# SH2_-_CONNECTORS.net
KiCad netlist of a schematic drawn in Altium Designer
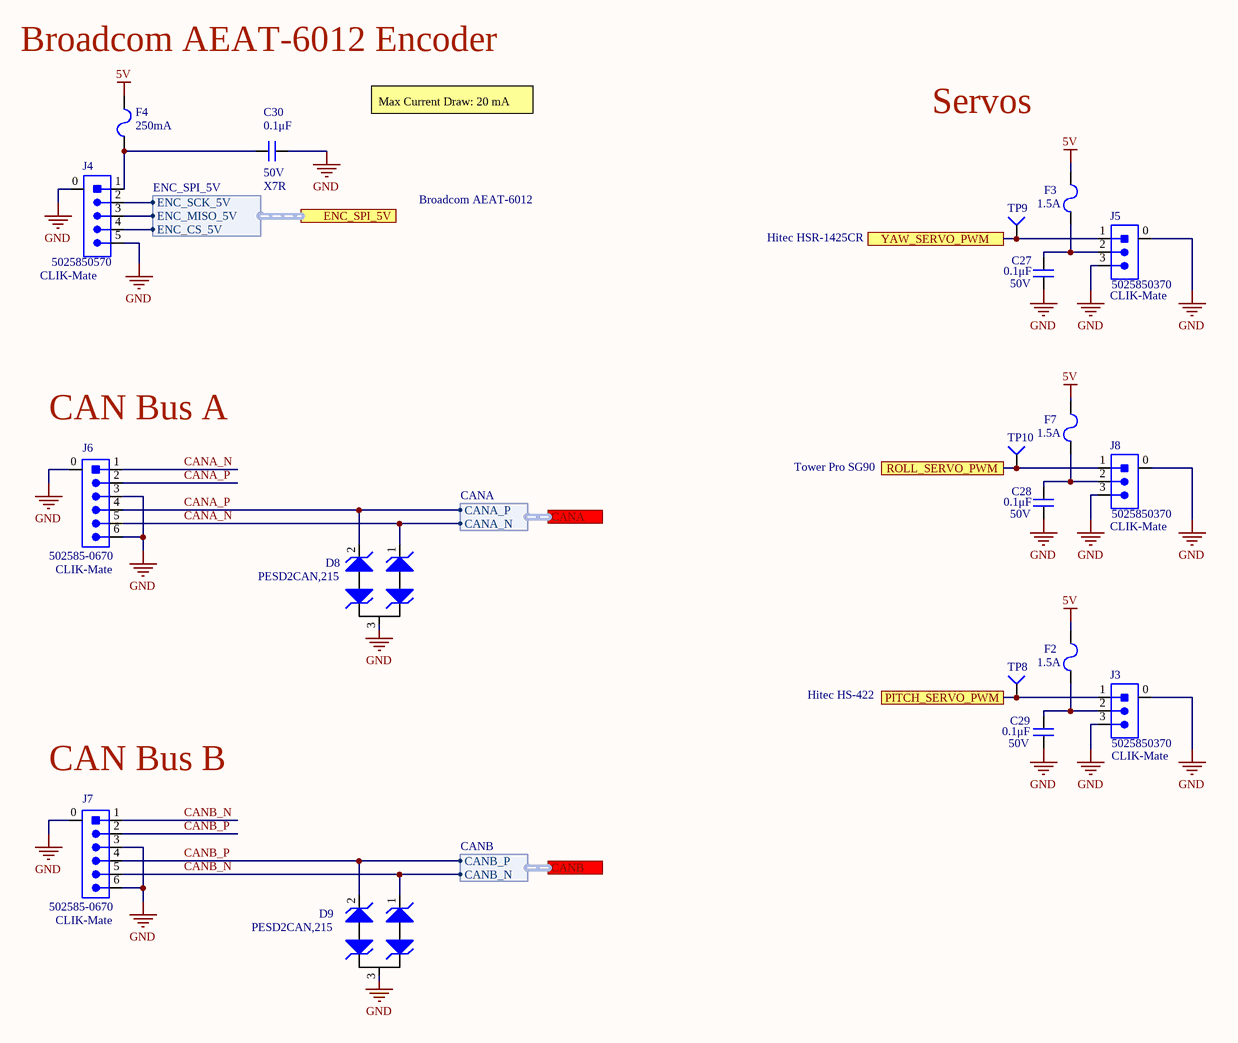
[diagram p0: SH2 - CONNECTORS.SchDoc]

(export (version "E")
  (design (tool "Eeschema 10.0.6"))
  (components
    (comp (ref "C27")
      (value "0.1μF")
      (footprint "CAP0603")
      (description "CAP CER 0.1UF 50V X7R 0603")
      (fields (field (name "VOLTAGE RATING") "50V") (field (name "Comment") "CAP_0.1uF_50V_0603"))
      (libsource (lib "UWRT_Schematic_Library_2020") (part "CAP_0.1uF_50V_0603"))
    )
    (comp (ref "C28")
      (value "0.1μF")
      (footprint "CAP0603")
      (description "CAP CER 0.1UF 50V X7R 0603")
      (fields (field (name "VOLTAGE RATING") "50V") (field (name "Comment") "CAP_0.1uF_50V_0603"))
      (libsource (lib "UWRT_Schematic_Library_2020") (part "CAP_0.1uF_50V_0603"))
    )
    (comp (ref "C29")
      (value "0.1μF")
      (footprint "CAP0603")
      (description "CAP CER 0.1UF 50V X7R 0603")
      (fields (field (name "VOLTAGE RATING") "50V") (field (name "Comment") "CAP_0.1uF_50V_0603"))
      (libsource (lib "UWRT_Schematic_Library_2020") (part "CAP_0.1uF_50V_0603"))
    )
    (comp (ref "C30")
      (value "0.1μF")
      (footprint "CAP0603")
      (description "CAP CER 0.1UF 50V X7R 0603")
      (fields
        (field (name "DIELECTRIC") "X7R")
        (field (name "VOLTAGE RATING") "50V")
        (field (name "Comment") "CAP_0.1uF_50V_0603")
      )
      (libsource (lib "UWRT_Schematic_Library_2020") (part "CAP_0.1uF_50V_0603"))
    )
    (comp (ref "D8")
      (value "TVS_DIODE_CAN")
      (footprint "TVS_DIODE_CAN")
      (description "TVS DIODE 24V 41V SOT323-3")
      (fields (field (name "MANUFACTURER PART NUMBER 1") "PESD2CAN,215"))
      (libsource (lib "UWRT_Schematic_Library_2020") (part "TVS_DIODE_CAN"))
    )
    (comp (ref "D9")
      (value "TVS_DIODE_CAN")
      (footprint "TVS_DIODE_CAN")
      (description "TVS DIODE 24V 41V SOT323-3")
      (fields (field (name "MANUFACTURER PART NUMBER 1") "PESD2CAN,215"))
      (libsource (lib "UWRT_Schematic_Library_2020") (part "TVS_DIODE_CAN"))
    )
    (comp (ref "F2")
      (value "FUSE_1.5A_1206")
      (footprint "FUSE_1206")
      (description "FUSE SMD 1.5A 63V")
      (fields (field (name "CURRENT RATING") "1.5A"))
      (libsource (lib "UWRT_Schematic_Library_2020") (part "FUSE_1.5A_1206"))
    )
    (comp (ref "F3")
      (value "FUSE_1.5A_1206")
      (footprint "FUSE_1206")
      (description "FUSE SMD 1.5A 63V")
      (fields (field (name "CURRENT RATING") "1.5A"))
      (libsource (lib "UWRT_Schematic_Library_2020") (part "FUSE_1.5A_1206"))
    )
    (comp (ref "F4")
      (value "FUSE_250mA_0603")
      (footprint "FUSE_0603")
      (description "FUSE SMD 250mA 32V")
      (fields (field (name "CURRENT RATING") "250mA"))
      (libsource (lib "UWRT_Schematic_Library_2020") (part "FUSE_250mA_0603"))
    )
    (comp (ref "F7")
      (value "FUSE_1.5A_1206")
      (footprint "FUSE_1206")
      (description "FUSE SMD 1.5A 63V")
      (fields (field (name "CURRENT RATING") "1.5A"))
      (libsource (lib "UWRT_Schematic_Library_2020") (part "FUSE_1.5A_1206"))
    )
    (comp (ref "J3")
      (value "CON_3M_SM_RA")
      (footprint "MOLEX-5025850370")
      (description "CONN RCPT 3POS 0.059 TIN SMD R/A")
      (fields (field (name "MANUFACTURER PART NUMBER 1") "5025850370") (field (name "FAMILY") "CLIK-Mate"))
      (libsource (lib "UWRT_Schematic_Library_2020") (part "CON_3M_SM_RA"))
    )
    (comp (ref "J4")
      (value "CON_5M_SM_RA")
      (footprint "MOLEX-5025850570")
      (description "CONN HEADER SMD RIGHT ANGLE 1.5MM PITCH")
      (fields (field (name "MANUFACTURER PART NUMBER 1") "5025850570") (field (name "FAMILY") "CLIK-Mate"))
      (libsource (lib "UWRT_Schematic_Library_2020") (part "CON_5M_SM_RA"))
    )
    (comp (ref "J5")
      (value "CON_3M_SM_RA")
      (footprint "MOLEX-5025850370")
      (description "CONN RCPT 3POS 0.059 TIN SMD R/A")
      (fields (field (name "MANUFACTURER PART NUMBER 1") "5025850370") (field (name "FAMILY") "CLIK-Mate"))
      (libsource (lib "UWRT_Schematic_Library_2020") (part "CON_3M_SM_RA"))
    )
    (comp (ref "J6")
      (value "CON_6M_SM_RA_1.5mm")
      (footprint "MOLEX-5025850670")
      (description "CONN HEADER SMD RIGHT ANGLE 1.5 MM PITCH")
      (fields
        (field (name "MANUFACTURER") "Molex")
        (field (name "FAMILY") "CLIK-Mate")
        (field (name "MANUFACTOR NUMBER") "502585-0670")
      )
      (libsource (lib "UWRT_Schematic_Library_2020") (part "CON_6M_SM_RA_1.5mm"))
    )
    (comp (ref "J7")
      (value "CON_6M_SM_RA_1.5mm")
      (footprint "MOLEX-5025850670")
      (description "CONN HEADER SMD RIGHT ANGLE 1.5 MM PITCH")
      (fields
        (field (name "MANUFACTURER") "Molex")
        (field (name "FAMILY") "CLIK-Mate")
        (field (name "MANUFACTOR NUMBER") "502585-0670")
      )
      (libsource (lib "UWRT_Schematic_Library_2020") (part "CON_6M_SM_RA_1.5mm"))
    )
    (comp (ref "J8")
      (value "CON_3M_SM_RA")
      (footprint "MOLEX-5025850370")
      (description "CONN RCPT 3POS 0.059 TIN SMD R/A")
      (fields (field (name "MANUFACTURER PART NUMBER 1") "5025850370") (field (name "FAMILY") "CLIK-Mate"))
      (libsource (lib "UWRT_Schematic_Library_2020") (part "CON_3M_SM_RA"))
    )
    (comp (ref "TP8")
      (value "TESTPOINT_1MM_CIRCLE")
      (footprint "TESTPOINT_CIRCLE_1MM")
      (description "TESTPOINT 1MM CIRCLE")
      (libsource (lib "UWRT_Schematic_Library_2020") (part "TESTPOINT_1MM_CIRCLE"))
    )
    (comp (ref "TP9")
      (value "TESTPOINT_1MM_CIRCLE")
      (footprint "TESTPOINT_CIRCLE_1MM")
      (description "TESTPOINT 1MM CIRCLE")
      (libsource (lib "UWRT_Schematic_Library_2020") (part "TESTPOINT_1MM_CIRCLE"))
    )
    (comp (ref "TP10")
      (value "TESTPOINT_1MM_CIRCLE")
      (footprint "TESTPOINT_CIRCLE_1MM")
      (description "TESTPOINT 1MM CIRCLE")
      (libsource (lib "UWRT_Schematic_Library_2020") (part "TESTPOINT_1MM_CIRCLE"))
    )
  )
  (nets
    (net (code "4") (name "/CANA_N") (class "Default")
      (node (ref "D8") (pin "1") (pinfunction "1_1") (pintype "passive"))
      (node (ref "J6") (pin "1") (pinfunction "1_1") (pintype "passive"))
      (node (ref "J6") (pin "5") (pinfunction "5_5") (pintype "passive"))
    )
    (net (code "5") (name "/CANA_P") (class "Default")
      (node (ref "D8") (pin "2") (pinfunction "2_2") (pintype "passive"))
      (node (ref "J6") (pin "2") (pinfunction "2_2") (pintype "passive"))
      (node (ref "J6") (pin "4") (pinfunction "4_4") (pintype "passive"))
    )
    (net (code "6") (name "/CANB_N") (class "Default")
      (node (ref "D9") (pin "1") (pinfunction "1_1") (pintype "passive"))
      (node (ref "J7") (pin "1") (pinfunction "1_1") (pintype "passive"))
      (node (ref "J7") (pin "5") (pinfunction "5_5") (pintype "passive"))
    )
    (net (code "7") (name "/CANB_P") (class "Default")
      (node (ref "D9") (pin "2") (pinfunction "2_2") (pintype "passive"))
      (node (ref "J7") (pin "2") (pinfunction "2_2") (pintype "passive"))
      (node (ref "J7") (pin "4") (pinfunction "4_4") (pintype "passive"))
    )
    (net (code "8") (name "/ENC_CS_5V") (class "Default")
      (node (ref "J4") (pin "4") (pinfunction "4_4") (pintype "passive"))
    )
    (net (code "9") (name "/ENC_MISO_5V") (class "Default")
      (node (ref "J4") (pin "3") (pinfunction "3_3") (pintype "passive"))
    )
    (net (code "10") (name "/ENC_SCK_5V") (class "Default")
      (node (ref "J4") (pin "2") (pinfunction "2_2") (pintype "passive"))
    )
    (net (code "11") (name "/PITCH_SERVO_PWM") (class "Default")
      (node (ref "J3") (pin "1") (pinfunction "1_1") (pintype "passive"))
      (node (ref "TP8") (pin "1") (pinfunction "=value_1") (pintype "passive"))
    )
    (net (code "12") (name "/ROLL_SERVO_PWM") (class "Default")
      (node (ref "J8") (pin "1") (pinfunction "1_1") (pintype "passive"))
      (node (ref "TP10") (pin "1") (pinfunction "=value_1") (pintype "passive"))
    )
    (net (code "13") (name "/YAW_SERVO_PWM") (class "Default")
      (node (ref "J5") (pin "1") (pinfunction "1_1") (pintype "passive"))
      (node (ref "TP9") (pin "1") (pinfunction "=value_1") (pintype "passive"))
    )
    (net (code "17") (name "5V") (class "Default")
      (node (ref "F2") (pin "2") (pinfunction "2_2") (pintype "passive"))
      (node (ref "F3") (pin "2") (pinfunction "2_2") (pintype "passive"))
      (node (ref "F4") (pin "2") (pinfunction "2_2") (pintype "passive"))
      (node (ref "F7") (pin "2") (pinfunction "2_2") (pintype "passive"))
    )
    (net (code "18") (name "GND") (class "Default")
      (node (ref "C27") (pin "1") (pinfunction "1_1") (pintype "passive"))
      (node (ref "C28") (pin "1") (pinfunction "1_1") (pintype "passive"))
      (node (ref "C29") (pin "1") (pinfunction "1_1") (pintype "passive"))
      (node (ref "C30") (pin "1") (pinfunction "1_1") (pintype "passive"))
      (node (ref "D8") (pin "3") (pinfunction "3_3") (pintype "passive"))
      (node (ref "D9") (pin "3") (pinfunction "3_3") (pintype "passive"))
      (node (ref "J3") (pin "0") (pinfunction "0_0") (pintype "passive"))
      (node (ref "J3") (pin "3") (pinfunction "3_3") (pintype "passive"))
      (node (ref "J4") (pin "0") (pinfunction "0_0") (pintype "passive"))
      (node (ref "J4") (pin "5") (pinfunction "5_5") (pintype "passive"))
      (node (ref "J5") (pin "0") (pinfunction "0_0") (pintype "passive"))
      (node (ref "J5") (pin "3") (pinfunction "3_3") (pintype "passive"))
      (node (ref "J6") (pin "0") (pinfunction "0_0") (pintype "passive"))
      (node (ref "J6") (pin "3") (pinfunction "3_3") (pintype "passive"))
      (node (ref "J6") (pin "6") (pinfunction "6_6") (pintype "passive"))
      (node (ref "J7") (pin "0") (pinfunction "0_0") (pintype "passive"))
      (node (ref "J7") (pin "3") (pinfunction "3_3") (pintype "passive"))
      (node (ref "J7") (pin "6") (pinfunction "6_6") (pintype "passive"))
      (node (ref "J8") (pin "0") (pinfunction "0_0") (pintype "passive"))
      (node (ref "J8") (pin "3") (pinfunction "3_3") (pintype "passive"))
    )
    (net (code "19") (name "Net-(C27-Pad2)") (class "Default")
      (node (ref "C27") (pin "2") (pinfunction "2_2") (pintype "passive"))
      (node (ref "F3") (pin "1") (pinfunction "1_1") (pintype "passive"))
      (node (ref "J5") (pin "2") (pinfunction "2_2") (pintype "passive"))
    )
    (net (code "20") (name "Net-(C28-Pad2)") (class "Default")
      (node (ref "C28") (pin "2") (pinfunction "2_2") (pintype "passive"))
      (node (ref "F7") (pin "1") (pinfunction "1_1") (pintype "passive"))
      (node (ref "J8") (pin "2") (pinfunction "2_2") (pintype "passive"))
    )
    (net (code "21") (name "Net-(C29-Pad2)") (class "Default")
      (node (ref "C29") (pin "2") (pinfunction "2_2") (pintype "passive"))
      (node (ref "F2") (pin "1") (pinfunction "1_1") (pintype "passive"))
      (node (ref "J3") (pin "2") (pinfunction "2_2") (pintype "passive"))
    )
    (net (code "22") (name "Net-(C30-Pad2)") (class "Default")
      (node (ref "C30") (pin "2") (pinfunction "2_2") (pintype "passive"))
      (node (ref "F4") (pin "1") (pinfunction "1_1") (pintype "passive"))
      (node (ref "J4") (pin "1") (pinfunction "1_1") (pintype "passive"))
    )
  )
)
